# PRJ_Camera_Light_V0_1a.net
KiCad netlist of a schematic drawn in EasyEDA Pro
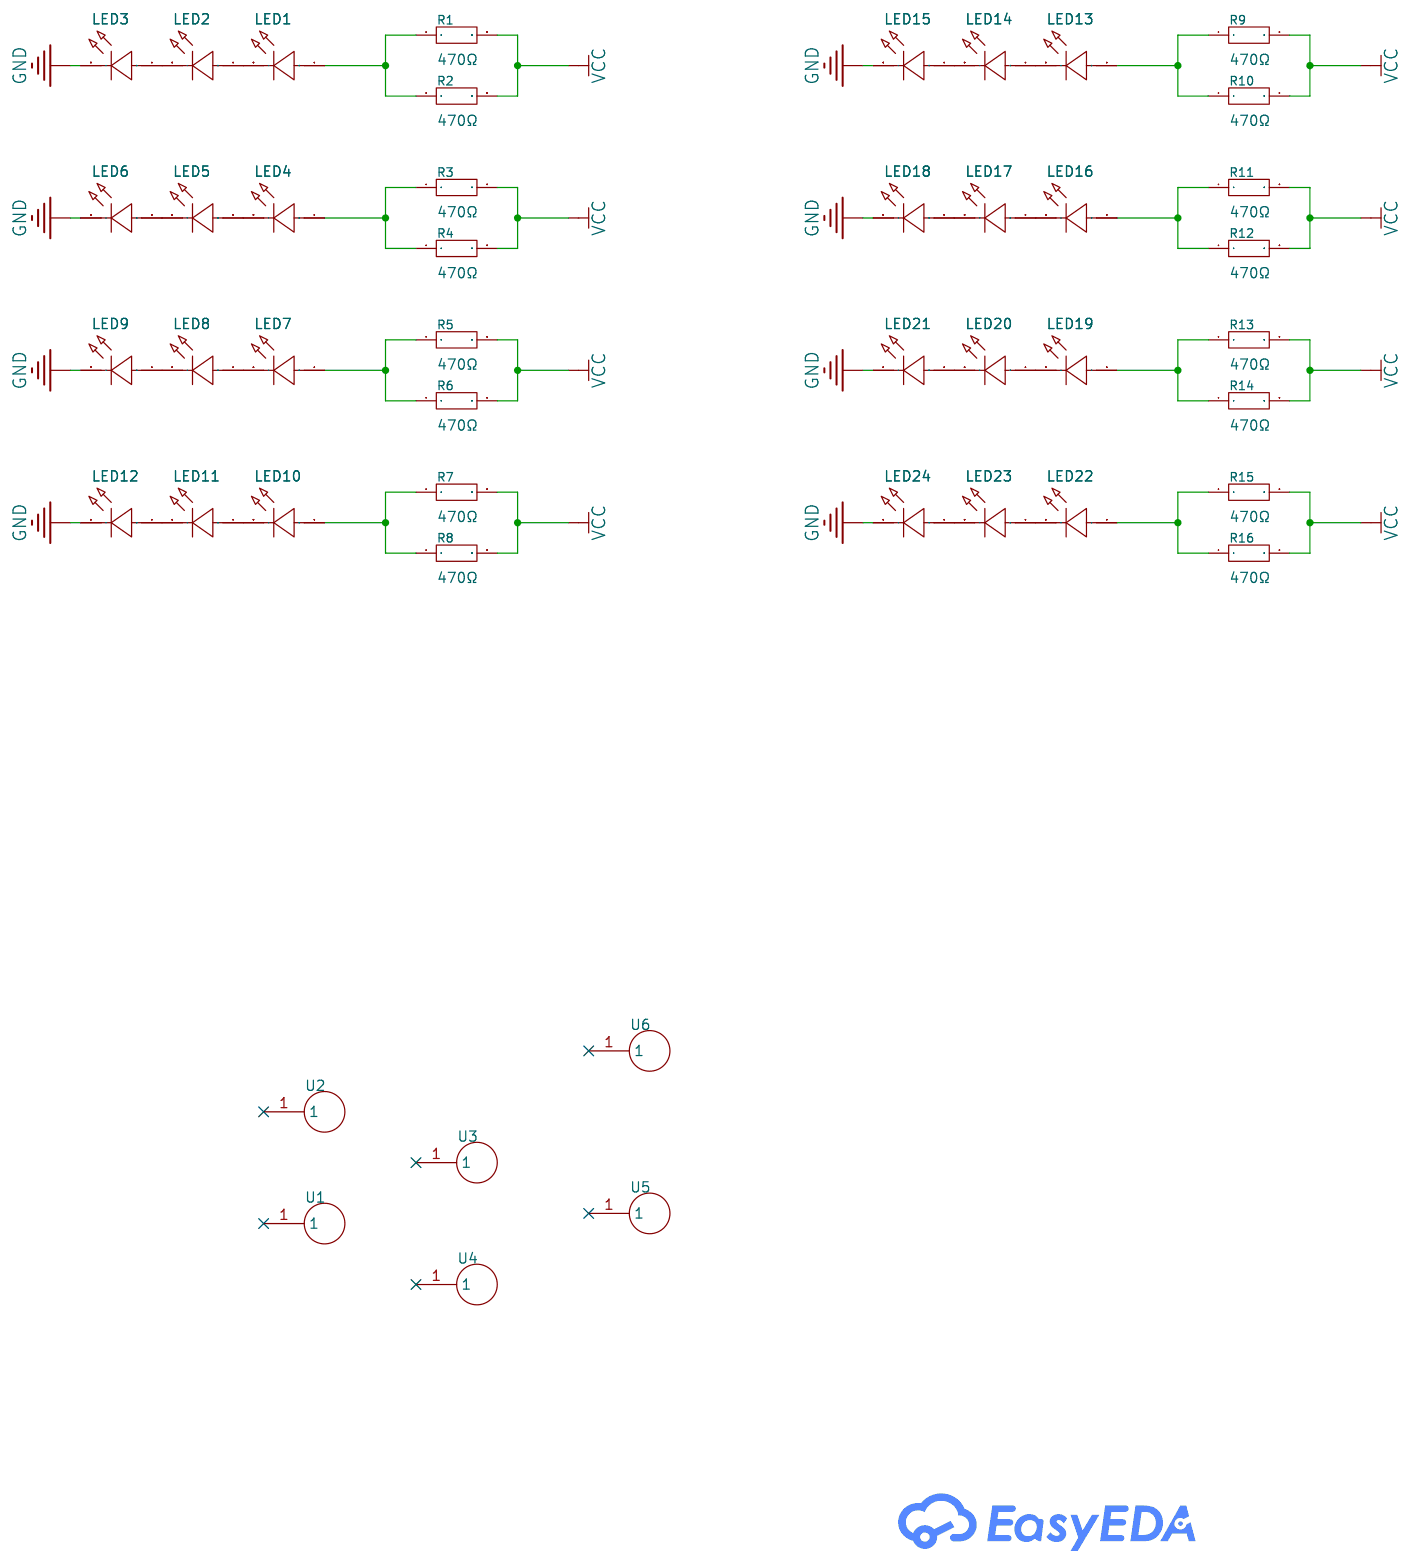
[diagram p0: schematic sheet]

(export (version "E")
  (design (tool "Eeschema 10.0.6"))
  (components
    (comp (ref "LED1")
      (value "SZYY1206W")
      (footprint "easyedapro:LED1206-R-RD_WHITE")
      (fields (field (name "Manufacturer") "yongyu(永裕光电)"))
      (libsource (lib "easyedapro") (part "SZYY1206W"))
    )
    (comp (ref "LED2")
      (value "SZYY1206W")
      (footprint "easyedapro:LED1206-R-RD_WHITE")
      (fields (field (name "Manufacturer") "yongyu(永裕光电)"))
      (libsource (lib "easyedapro") (part "SZYY1206W"))
    )
    (comp (ref "LED3")
      (value "SZYY1206W")
      (footprint "easyedapro:LED1206-R-RD_WHITE")
      (fields (field (name "Manufacturer") "yongyu(永裕光电)"))
      (libsource (lib "easyedapro") (part "SZYY1206W"))
    )
    (comp (ref "LED4")
      (value "SZYY1206W")
      (footprint "easyedapro:LED1206-R-RD_WHITE")
      (fields (field (name "Manufacturer") "yongyu(永裕光电)"))
      (libsource (lib "easyedapro") (part "SZYY1206W"))
    )
    (comp (ref "LED5")
      (value "SZYY1206W")
      (footprint "easyedapro:LED1206-R-RD_WHITE")
      (fields (field (name "Manufacturer") "yongyu(永裕光电)"))
      (libsource (lib "easyedapro") (part "SZYY1206W"))
    )
    (comp (ref "LED6")
      (value "SZYY1206W")
      (footprint "easyedapro:LED1206-R-RD_WHITE")
      (fields (field (name "Manufacturer") "yongyu(永裕光电)"))
      (libsource (lib "easyedapro") (part "SZYY1206W"))
    )
    (comp (ref "LED7")
      (value "SZYY1206W")
      (footprint "easyedapro:LED1206-R-RD_WHITE")
      (fields (field (name "Manufacturer") "yongyu(永裕光电)"))
      (libsource (lib "easyedapro") (part "SZYY1206W"))
    )
    (comp (ref "LED8")
      (value "SZYY1206W")
      (footprint "easyedapro:LED1206-R-RD_WHITE")
      (fields (field (name "Manufacturer") "yongyu(永裕光电)"))
      (libsource (lib "easyedapro") (part "SZYY1206W"))
    )
    (comp (ref "LED9")
      (value "SZYY1206W")
      (footprint "easyedapro:LED1206-R-RD_WHITE")
      (fields (field (name "Manufacturer") "yongyu(永裕光电)"))
      (libsource (lib "easyedapro") (part "SZYY1206W"))
    )
    (comp (ref "LED10")
      (value "SZYY1206W")
      (footprint "easyedapro:LED1206-R-RD_WHITE")
      (fields (field (name "Manufacturer") "yongyu(永裕光电)"))
      (libsource (lib "easyedapro") (part "SZYY1206W"))
    )
    (comp (ref "LED11")
      (value "SZYY1206W")
      (footprint "easyedapro:LED1206-R-RD_WHITE")
      (fields (field (name "Manufacturer") "yongyu(永裕光电)"))
      (libsource (lib "easyedapro") (part "SZYY1206W"))
    )
    (comp (ref "LED12")
      (value "SZYY1206W")
      (footprint "easyedapro:LED1206-R-RD_WHITE")
      (fields (field (name "Manufacturer") "yongyu(永裕光电)"))
      (libsource (lib "easyedapro") (part "SZYY1206W"))
    )
    (comp (ref "LED13")
      (value "SZYY1206W")
      (footprint "easyedapro:LED1206-R-RD_WHITE")
      (fields (field (name "Manufacturer") "yongyu(永裕光电)"))
      (libsource (lib "easyedapro") (part "SZYY1206W"))
    )
    (comp (ref "LED14")
      (value "SZYY1206W")
      (footprint "easyedapro:LED1206-R-RD_WHITE")
      (fields (field (name "Manufacturer") "yongyu(永裕光电)"))
      (libsource (lib "easyedapro") (part "SZYY1206W"))
    )
    (comp (ref "LED15")
      (value "SZYY1206W")
      (footprint "easyedapro:LED1206-R-RD_WHITE")
      (fields (field (name "Manufacturer") "yongyu(永裕光电)"))
      (libsource (lib "easyedapro") (part "SZYY1206W"))
    )
    (comp (ref "LED16")
      (value "SZYY1206W")
      (footprint "easyedapro:LED1206-R-RD_WHITE")
      (fields (field (name "Manufacturer") "yongyu(永裕光电)"))
      (libsource (lib "easyedapro") (part "SZYY1206W"))
    )
    (comp (ref "LED17")
      (value "SZYY1206W")
      (footprint "easyedapro:LED1206-R-RD_WHITE")
      (fields (field (name "Manufacturer") "yongyu(永裕光电)"))
      (libsource (lib "easyedapro") (part "SZYY1206W"))
    )
    (comp (ref "LED18")
      (value "SZYY1206W")
      (footprint "easyedapro:LED1206-R-RD_WHITE")
      (fields (field (name "Manufacturer") "yongyu(永裕光电)"))
      (libsource (lib "easyedapro") (part "SZYY1206W"))
    )
    (comp (ref "LED19")
      (value "SZYY1206W")
      (footprint "easyedapro:LED1206-R-RD_WHITE")
      (fields (field (name "Manufacturer") "yongyu(永裕光电)"))
      (libsource (lib "easyedapro") (part "SZYY1206W"))
    )
    (comp (ref "LED20")
      (value "SZYY1206W")
      (footprint "easyedapro:LED1206-R-RD_WHITE")
      (fields (field (name "Manufacturer") "yongyu(永裕光电)"))
      (libsource (lib "easyedapro") (part "SZYY1206W"))
    )
    (comp (ref "LED21")
      (value "SZYY1206W")
      (footprint "easyedapro:LED1206-R-RD_WHITE")
      (fields (field (name "Manufacturer") "yongyu(永裕光电)"))
      (libsource (lib "easyedapro") (part "SZYY1206W"))
    )
    (comp (ref "LED22")
      (value "SZYY1206W")
      (footprint "easyedapro:LED1206-R-RD_WHITE")
      (fields (field (name "Manufacturer") "yongyu(永裕光电)"))
      (libsource (lib "easyedapro") (part "SZYY1206W"))
    )
    (comp (ref "LED23")
      (value "SZYY1206W")
      (footprint "easyedapro:LED1206-R-RD_WHITE")
      (fields (field (name "Manufacturer") "yongyu(永裕光电)"))
      (libsource (lib "easyedapro") (part "SZYY1206W"))
    )
    (comp (ref "LED24")
      (value "SZYY1206W")
      (footprint "easyedapro:LED1206-R-RD_WHITE")
      (fields (field (name "Manufacturer") "yongyu(永裕光电)"))
      (libsource (lib "easyedapro") (part "SZYY1206W"))
    )
    (comp (ref "R1")
      (value "470Ω")
      (footprint "easyedapro:R0805")
      (fields
        (field (name "Manufacturer Part") "0805W8F4700T5E")
        (field (name "Manufacturer") "UNI-ROYAL(厚声)")
      )
      (libsource (lib "easyedapro") (part "0805W8F4700T5E"))
    )
    (comp (ref "R2")
      (value "470Ω")
      (footprint "easyedapro:R0805")
      (fields
        (field (name "Manufacturer Part") "0805W8F4700T5E")
        (field (name "Manufacturer") "UNI-ROYAL(厚声)")
      )
      (libsource (lib "easyedapro") (part "0805W8F4700T5E"))
    )
    (comp (ref "R3")
      (value "470Ω")
      (footprint "easyedapro:R0805")
      (fields
        (field (name "Manufacturer Part") "0805W8F4700T5E")
        (field (name "Manufacturer") "UNI-ROYAL(厚声)")
      )
      (libsource (lib "easyedapro") (part "0805W8F4700T5E"))
    )
    (comp (ref "R4")
      (value "470Ω")
      (footprint "easyedapro:R0805")
      (fields
        (field (name "Manufacturer Part") "0805W8F4700T5E")
        (field (name "Manufacturer") "UNI-ROYAL(厚声)")
      )
      (libsource (lib "easyedapro") (part "0805W8F4700T5E"))
    )
    (comp (ref "R5")
      (value "470Ω")
      (footprint "easyedapro:R0805")
      (fields
        (field (name "Manufacturer Part") "0805W8F4700T5E")
        (field (name "Manufacturer") "UNI-ROYAL(厚声)")
      )
      (libsource (lib "easyedapro") (part "0805W8F4700T5E"))
    )
    (comp (ref "R6")
      (value "470Ω")
      (footprint "easyedapro:R0805")
      (fields
        (field (name "Manufacturer Part") "0805W8F4700T5E")
        (field (name "Manufacturer") "UNI-ROYAL(厚声)")
      )
      (libsource (lib "easyedapro") (part "0805W8F4700T5E"))
    )
    (comp (ref "R7")
      (value "470Ω")
      (footprint "easyedapro:R0805")
      (fields
        (field (name "Manufacturer Part") "0805W8F4700T5E")
        (field (name "Manufacturer") "UNI-ROYAL(厚声)")
      )
      (libsource (lib "easyedapro") (part "0805W8F4700T5E"))
    )
    (comp (ref "R8")
      (value "470Ω")
      (footprint "easyedapro:R0805")
      (fields
        (field (name "Manufacturer Part") "0805W8F4700T5E")
        (field (name "Manufacturer") "UNI-ROYAL(厚声)")
      )
      (libsource (lib "easyedapro") (part "0805W8F4700T5E"))
    )
    (comp (ref "R9")
      (value "470Ω")
      (footprint "easyedapro:R0805")
      (fields
        (field (name "Manufacturer Part") "0805W8F4700T5E")
        (field (name "Manufacturer") "UNI-ROYAL(厚声)")
      )
      (libsource (lib "easyedapro") (part "0805W8F4700T5E"))
    )
    (comp (ref "R10")
      (value "470Ω")
      (footprint "easyedapro:R0805")
      (fields
        (field (name "Manufacturer Part") "0805W8F4700T5E")
        (field (name "Manufacturer") "UNI-ROYAL(厚声)")
      )
      (libsource (lib "easyedapro") (part "0805W8F4700T5E"))
    )
    (comp (ref "R11")
      (value "470Ω")
      (footprint "easyedapro:R0805")
      (fields
        (field (name "Manufacturer Part") "0805W8F4700T5E")
        (field (name "Manufacturer") "UNI-ROYAL(厚声)")
      )
      (libsource (lib "easyedapro") (part "0805W8F4700T5E"))
    )
    (comp (ref "R12")
      (value "470Ω")
      (footprint "easyedapro:R0805")
      (fields
        (field (name "Manufacturer Part") "0805W8F4700T5E")
        (field (name "Manufacturer") "UNI-ROYAL(厚声)")
      )
      (libsource (lib "easyedapro") (part "0805W8F4700T5E"))
    )
    (comp (ref "R13")
      (value "470Ω")
      (footprint "easyedapro:R0805")
      (fields
        (field (name "Manufacturer Part") "0805W8F4700T5E")
        (field (name "Manufacturer") "UNI-ROYAL(厚声)")
      )
      (libsource (lib "easyedapro") (part "0805W8F4700T5E"))
    )
    (comp (ref "R14")
      (value "470Ω")
      (footprint "easyedapro:R0805")
      (fields
        (field (name "Manufacturer Part") "0805W8F4700T5E")
        (field (name "Manufacturer") "UNI-ROYAL(厚声)")
      )
      (libsource (lib "easyedapro") (part "0805W8F4700T5E"))
    )
    (comp (ref "R15")
      (value "470Ω")
      (footprint "easyedapro:R0805")
      (fields
        (field (name "Manufacturer Part") "0805W8F4700T5E")
        (field (name "Manufacturer") "UNI-ROYAL(厚声)")
      )
      (libsource (lib "easyedapro") (part "0805W8F4700T5E"))
    )
    (comp (ref "R16")
      (value "470Ω")
      (footprint "easyedapro:R0805")
      (fields
        (field (name "Manufacturer Part") "0805W8F4700T5E")
        (field (name "Manufacturer") "UNI-ROYAL(厚声)")
      )
      (libsource (lib "easyedapro") (part "0805W8F4700T5E"))
    )
    (comp (ref "U1")
      (value "~")
      (footprint "easyedapro:FID_CUST")
      (description "Custom 1MM fiducial")
      (libsource (lib "easyedapro") (part "FID_CUST"))
    )
    (comp (ref "U2")
      (value "~")
      (footprint "easyedapro:FID_CUST")
      (description "Custom 1MM fiducial")
      (libsource (lib "easyedapro") (part "FID_CUST"))
    )
    (comp (ref "U3")
      (value "~")
      (footprint "easyedapro:FID_CUST")
      (description "Custom 1MM fiducial")
      (libsource (lib "easyedapro") (part "FID_CUST"))
    )
    (comp (ref "U4")
      (value "~")
      (footprint "easyedapro:FID_CUST")
      (description "Custom 1MM fiducial")
      (libsource (lib "easyedapro") (part "FID_CUST"))
    )
    (comp (ref "U5")
      (value "~")
      (footprint "easyedapro:FID_CUST")
      (description "Custom 1MM fiducial")
      (libsource (lib "easyedapro") (part "FID_CUST"))
    )
    (comp (ref "U6")
      (value "~")
      (footprint "easyedapro:FID_CUST")
      (description "Custom 1MM fiducial")
      (libsource (lib "easyedapro") (part "FID_CUST"))
    )
  )
  (nets
    (net (code "1") (name "GND") (class "Default")
      (node (ref "LED12") (pin "2") (pinfunction "-_2") (pintype "unspecified"))
      (node (ref "LED15") (pin "2") (pinfunction "-_2") (pintype "unspecified"))
      (node (ref "LED18") (pin "2") (pinfunction "-_2") (pintype "unspecified"))
      (node (ref "LED21") (pin "2") (pinfunction "-_2") (pintype "unspecified"))
      (node (ref "LED24") (pin "2") (pinfunction "-_2") (pintype "unspecified"))
      (node (ref "LED3") (pin "2") (pinfunction "-_2") (pintype "unspecified"))
      (node (ref "LED6") (pin "2") (pinfunction "-_2") (pintype "unspecified"))
      (node (ref "LED9") (pin "2") (pinfunction "-_2") (pintype "unspecified"))
    )
    (net (code "2") (name "Net-(LED1-+)") (class "Default")
      (node (ref "LED1") (pin "1") (pinfunction "+_1") (pintype "unspecified"))
      (node (ref "R1") (pin "1") (pinfunction "1_1") (pintype "input"))
      (node (ref "R2") (pin "1") (pinfunction "1_1") (pintype "input"))
    )
    (net (code "3") (name "Net-(LED1--)") (class "Default")
      (node (ref "LED1") (pin "2") (pinfunction "-_2") (pintype "unspecified"))
      (node (ref "LED2") (pin "1") (pinfunction "+_1") (pintype "unspecified"))
    )
    (net (code "4") (name "Net-(LED2--)") (class "Default")
      (node (ref "LED2") (pin "2") (pinfunction "-_2") (pintype "unspecified"))
      (node (ref "LED3") (pin "1") (pinfunction "+_1") (pintype "unspecified"))
    )
    (net (code "5") (name "Net-(LED4-+)") (class "Default")
      (node (ref "LED4") (pin "1") (pinfunction "+_1") (pintype "unspecified"))
      (node (ref "R3") (pin "1") (pinfunction "1_1") (pintype "input"))
      (node (ref "R4") (pin "1") (pinfunction "1_1") (pintype "input"))
    )
    (net (code "6") (name "Net-(LED4--)") (class "Default")
      (node (ref "LED4") (pin "2") (pinfunction "-_2") (pintype "unspecified"))
      (node (ref "LED5") (pin "1") (pinfunction "+_1") (pintype "unspecified"))
    )
    (net (code "7") (name "Net-(LED5--)") (class "Default")
      (node (ref "LED5") (pin "2") (pinfunction "-_2") (pintype "unspecified"))
      (node (ref "LED6") (pin "1") (pinfunction "+_1") (pintype "unspecified"))
    )
    (net (code "8") (name "Net-(LED7-+)") (class "Default")
      (node (ref "LED7") (pin "1") (pinfunction "+_1") (pintype "unspecified"))
      (node (ref "R5") (pin "1") (pinfunction "1_1") (pintype "input"))
      (node (ref "R6") (pin "1") (pinfunction "1_1") (pintype "input"))
    )
    (net (code "9") (name "Net-(LED7--)") (class "Default")
      (node (ref "LED7") (pin "2") (pinfunction "-_2") (pintype "unspecified"))
      (node (ref "LED8") (pin "1") (pinfunction "+_1") (pintype "unspecified"))
    )
    (net (code "10") (name "Net-(LED8--)") (class "Default")
      (node (ref "LED8") (pin "2") (pinfunction "-_2") (pintype "unspecified"))
      (node (ref "LED9") (pin "1") (pinfunction "+_1") (pintype "unspecified"))
    )
    (net (code "11") (name "Net-(LED10-+)") (class "Default")
      (node (ref "LED10") (pin "1") (pinfunction "+_1") (pintype "unspecified"))
      (node (ref "R7") (pin "1") (pinfunction "1_1") (pintype "input"))
      (node (ref "R8") (pin "1") (pinfunction "1_1") (pintype "input"))
    )
    (net (code "12") (name "Net-(LED10--)") (class "Default")
      (node (ref "LED10") (pin "2") (pinfunction "-_2") (pintype "unspecified"))
      (node (ref "LED11") (pin "1") (pinfunction "+_1") (pintype "unspecified"))
    )
    (net (code "13") (name "Net-(LED11--)") (class "Default")
      (node (ref "LED11") (pin "2") (pinfunction "-_2") (pintype "unspecified"))
      (node (ref "LED12") (pin "1") (pinfunction "+_1") (pintype "unspecified"))
    )
    (net (code "14") (name "Net-(LED13-+)") (class "Default")
      (node (ref "LED13") (pin "1") (pinfunction "+_1") (pintype "unspecified"))
      (node (ref "R10") (pin "1") (pinfunction "1_1") (pintype "input"))
      (node (ref "R9") (pin "1") (pinfunction "1_1") (pintype "input"))
    )
    (net (code "15") (name "Net-(LED13--)") (class "Default")
      (node (ref "LED13") (pin "2") (pinfunction "-_2") (pintype "unspecified"))
      (node (ref "LED14") (pin "1") (pinfunction "+_1") (pintype "unspecified"))
    )
    (net (code "16") (name "Net-(LED14--)") (class "Default")
      (node (ref "LED14") (pin "2") (pinfunction "-_2") (pintype "unspecified"))
      (node (ref "LED15") (pin "1") (pinfunction "+_1") (pintype "unspecified"))
    )
    (net (code "17") (name "Net-(LED16-+)") (class "Default")
      (node (ref "LED16") (pin "1") (pinfunction "+_1") (pintype "unspecified"))
      (node (ref "R11") (pin "1") (pinfunction "1_1") (pintype "input"))
      (node (ref "R12") (pin "1") (pinfunction "1_1") (pintype "input"))
    )
    (net (code "18") (name "Net-(LED16--)") (class "Default")
      (node (ref "LED16") (pin "2") (pinfunction "-_2") (pintype "unspecified"))
      (node (ref "LED17") (pin "1") (pinfunction "+_1") (pintype "unspecified"))
    )
    (net (code "19") (name "Net-(LED17--)") (class "Default")
      (node (ref "LED17") (pin "2") (pinfunction "-_2") (pintype "unspecified"))
      (node (ref "LED18") (pin "1") (pinfunction "+_1") (pintype "unspecified"))
    )
    (net (code "20") (name "Net-(LED19-+)") (class "Default")
      (node (ref "LED19") (pin "1") (pinfunction "+_1") (pintype "unspecified"))
      (node (ref "R13") (pin "1") (pinfunction "1_1") (pintype "input"))
      (node (ref "R14") (pin "1") (pinfunction "1_1") (pintype "input"))
    )
    (net (code "21") (name "Net-(LED19--)") (class "Default")
      (node (ref "LED19") (pin "2") (pinfunction "-_2") (pintype "unspecified"))
      (node (ref "LED20") (pin "1") (pinfunction "+_1") (pintype "unspecified"))
    )
    (net (code "22") (name "Net-(LED20--)") (class "Default")
      (node (ref "LED20") (pin "2") (pinfunction "-_2") (pintype "unspecified"))
      (node (ref "LED21") (pin "1") (pinfunction "+_1") (pintype "unspecified"))
    )
    (net (code "23") (name "Net-(LED22-+)") (class "Default")
      (node (ref "LED22") (pin "1") (pinfunction "+_1") (pintype "unspecified"))
      (node (ref "R15") (pin "1") (pinfunction "1_1") (pintype "input"))
      (node (ref "R16") (pin "1") (pinfunction "1_1") (pintype "input"))
    )
    (net (code "24") (name "Net-(LED22--)") (class "Default")
      (node (ref "LED22") (pin "2") (pinfunction "-_2") (pintype "unspecified"))
      (node (ref "LED23") (pin "1") (pinfunction "+_1") (pintype "unspecified"))
    )
    (net (code "25") (name "Net-(LED23--)") (class "Default")
      (node (ref "LED23") (pin "2") (pinfunction "-_2") (pintype "unspecified"))
      (node (ref "LED24") (pin "1") (pinfunction "+_1") (pintype "unspecified"))
    )
    (net (code "26") (name "VCC") (class "Default")
      (node (ref "R1") (pin "2") (pinfunction "2_2") (pintype "input"))
      (node (ref "R10") (pin "2") (pinfunction "2_2") (pintype "input"))
      (node (ref "R11") (pin "2") (pinfunction "2_2") (pintype "input"))
      (node (ref "R12") (pin "2") (pinfunction "2_2") (pintype "input"))
      (node (ref "R13") (pin "2") (pinfunction "2_2") (pintype "input"))
      (node (ref "R14") (pin "2") (pinfunction "2_2") (pintype "input"))
      (node (ref "R15") (pin "2") (pinfunction "2_2") (pintype "input"))
      (node (ref "R16") (pin "2") (pinfunction "2_2") (pintype "input"))
      (node (ref "R2") (pin "2") (pinfunction "2_2") (pintype "input"))
      (node (ref "R3") (pin "2") (pinfunction "2_2") (pintype "input"))
      (node (ref "R4") (pin "2") (pinfunction "2_2") (pintype "input"))
      (node (ref "R5") (pin "2") (pinfunction "2_2") (pintype "input"))
      (node (ref "R6") (pin "2") (pinfunction "2_2") (pintype "input"))
      (node (ref "R7") (pin "2") (pinfunction "2_2") (pintype "input"))
      (node (ref "R8") (pin "2") (pinfunction "2_2") (pintype "input"))
      (node (ref "R9") (pin "2") (pinfunction "2_2") (pintype "input"))
    )
    (net (code "27") (name "unconnected-(U1-Pad1)") (class "Default")
      (node (ref "U1") (pin "1") (pinfunction "1_1") (pintype "input+no_connect"))
    )
    (net (code "28") (name "unconnected-(U2-Pad1)") (class "Default")
      (node (ref "U2") (pin "1") (pinfunction "1_1") (pintype "input+no_connect"))
    )
    (net (code "29") (name "unconnected-(U3-Pad1)") (class "Default")
      (node (ref "U3") (pin "1") (pinfunction "1_1") (pintype "input+no_connect"))
    )
    (net (code "30") (name "unconnected-(U4-Pad1)") (class "Default")
      (node (ref "U4") (pin "1") (pinfunction "1_1") (pintype "input+no_connect"))
    )
    (net (code "31") (name "unconnected-(U5-Pad1)") (class "Default")
      (node (ref "U5") (pin "1") (pinfunction "1_1") (pintype "input+no_connect"))
    )
    (net (code "32") (name "unconnected-(U6-Pad1)") (class "Default")
      (node (ref "U6") (pin "1") (pinfunction "1_1") (pintype "input+no_connect"))
    )
  )
)
